# main.net
KiCad netlist of a schematic drawn in Altium Designer
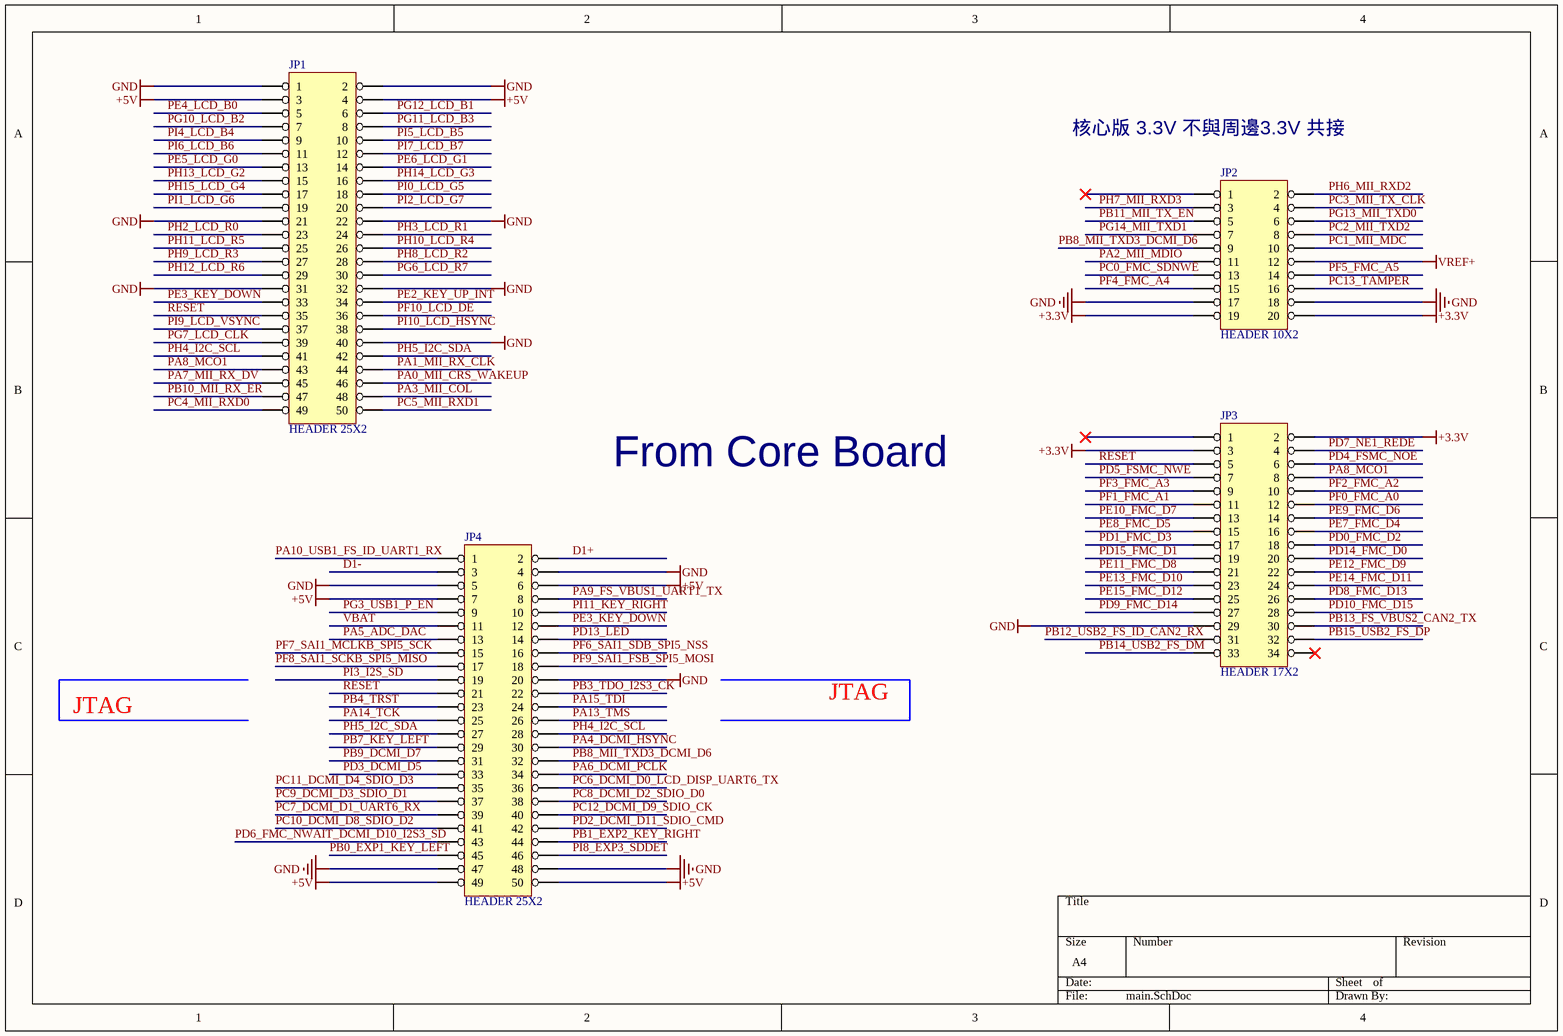
[diagram p0: main.SchDoc]

(export (version "E")
  (design (tool "Eeschema 10.0.6"))
  (components
    (comp (ref "JP1")
      (value "HEADER 25X2")
      (footprint "SIP-50-1.27-SMD")
      (libsource (lib "Mini-STM32F4x9IG-DK-B-SCH") (part "HEADER 25X2"))
    )
    (comp (ref "JP2")
      (value "HEADER 10X2")
      (footprint "SIP-20-1.27-SMD")
      (libsource (lib "Mini-STM32F4x9IG-DK-B-SCH") (part "HEADER 10X2"))
    )
    (comp (ref "JP3")
      (value "HEADER 17X2")
      (footprint "SIP-34-1.27-SMD")
      (libsource (lib "Mini-STM32F4x9IG-DK-B-SCH") (part "HEADER 17X2"))
    )
    (comp (ref "JP4")
      (value "HEADER 25X2")
      (footprint "SIP-50-1.27-SMD")
      (libsource (lib "Mini-STM32F4x9IG-DK-B-SCH") (part "HEADER 25X2"))
    )
  )
  (nets
    (net (code "1") (name "+3.3V") (class "Default")
      (node (ref "JP2") (pin "19") (pinfunction "19_19") (pintype "passive"))
      (node (ref "JP2") (pin "20") (pinfunction "20_20") (pintype "passive"))
      (node (ref "JP3") (pin "2") (pinfunction "2_2") (pintype "passive"))
      (node (ref "JP3") (pin "3") (pinfunction "3_3") (pintype "passive"))
    )
    (net (code "2") (name "+5V") (class "Default")
      (node (ref "JP1") (pin "3") (pinfunction "3_3") (pintype "passive"))
      (node (ref "JP1") (pin "4") (pinfunction "4_4") (pintype "passive"))
      (node (ref "JP4") (pin "49") (pinfunction "49_49") (pintype "passive"))
      (node (ref "JP4") (pin "50") (pinfunction "50_50") (pintype "passive"))
      (node (ref "JP4") (pin "6") (pinfunction "6_6") (pintype "passive"))
      (node (ref "JP4") (pin "7") (pinfunction "7_7") (pintype "passive"))
    )
    (net (code "3") (name "/D1+") (class "Default")
      (node (ref "JP4") (pin "2") (pinfunction "2_2") (pintype "passive"))
    )
    (net (code "4") (name "/D1-") (class "Default")
      (node (ref "JP4") (pin "3") (pinfunction "3_3") (pintype "passive"))
    )
    (net (code "5") (name "/PA0_MII_CRS_WAKEUP") (class "Default")
      (node (ref "JP1") (pin "46") (pinfunction "46_46") (pintype "passive"))
    )
    (net (code "6") (name "/PA1_MII_RX_CLK") (class "Default")
      (node (ref "JP1") (pin "44") (pinfunction "44_44") (pintype "passive"))
    )
    (net (code "7") (name "/PA2_MII_MDIO") (class "Default")
      (node (ref "JP2") (pin "11") (pinfunction "11_11") (pintype "passive"))
    )
    (net (code "8") (name "/PA3_MII_COL") (class "Default")
      (node (ref "JP1") (pin "48") (pinfunction "48_48") (pintype "passive"))
    )
    (net (code "9") (name "/PA4_DCMI_HSYNC") (class "Default")
      (node (ref "JP4") (pin "30") (pinfunction "30_30") (pintype "passive"))
    )
    (net (code "10") (name "/PA5_ADC_DAC") (class "Default")
      (node (ref "JP4") (pin "13") (pinfunction "13_13") (pintype "passive"))
    )
    (net (code "11") (name "/PA6_DCMI_PCLK") (class "Default")
      (node (ref "JP4") (pin "34") (pinfunction "34_34") (pintype "passive"))
    )
    (net (code "12") (name "/PA7_MII_RX_DV") (class "Default")
      (node (ref "JP1") (pin "45") (pinfunction "45_45") (pintype "passive"))
    )
    (net (code "13") (name "/PA8_MCO1") (class "Default")
      (node (ref "JP1") (pin "43") (pinfunction "43_43") (pintype "passive"))
      (node (ref "JP3") (pin "8") (pinfunction "8_8") (pintype "passive"))
    )
    (net (code "14") (name "/PA9_FS_VBUS1_UART1_TX") (class "Default")
      (node (ref "JP4") (pin "8") (pinfunction "8_8") (pintype "passive"))
    )
    (net (code "15") (name "/PA10_USB1_FS_ID_UART1_RX") (class "Default")
      (node (ref "JP4") (pin "1") (pinfunction "1_1") (pintype "passive"))
    )
    (net (code "16") (name "/PA13_TMS") (class "Default")
      (node (ref "JP4") (pin "26") (pinfunction "26_26") (pintype "passive"))
    )
    (net (code "17") (name "/PA14_TCK") (class "Default")
      (node (ref "JP4") (pin "25") (pinfunction "25_25") (pintype "passive"))
    )
    (net (code "18") (name "/PA15_TDI") (class "Default")
      (node (ref "JP4") (pin "24") (pinfunction "24_24") (pintype "passive"))
    )
    (net (code "19") (name "/PB0_EXP1_KEY_LEFT") (class "Default")
      (node (ref "JP4") (pin "45") (pinfunction "45_45") (pintype "passive"))
    )
    (net (code "20") (name "/PB1_EXP2_KEY_RIGHT") (class "Default")
      (node (ref "JP4") (pin "44") (pinfunction "44_44") (pintype "passive"))
    )
    (net (code "21") (name "/PB3_TDO_I2S3_CK") (class "Default")
      (node (ref "JP4") (pin "22") (pinfunction "22_22") (pintype "passive"))
    )
    (net (code "22") (name "/PB4_TRST") (class "Default")
      (node (ref "JP4") (pin "23") (pinfunction "23_23") (pintype "passive"))
    )
    (net (code "23") (name "/PB7_KEY_LEFT") (class "Default")
      (node (ref "JP4") (pin "29") (pinfunction "29_29") (pintype "passive"))
    )
    (net (code "24") (name "/PB8_MII_TXD3_DCMI_D6") (class "Default")
      (node (ref "JP2") (pin "9") (pinfunction "9_9") (pintype "passive"))
      (node (ref "JP4") (pin "32") (pinfunction "32_32") (pintype "passive"))
    )
    (net (code "25") (name "/PB9_DCMI_D7") (class "Default")
      (node (ref "JP4") (pin "31") (pinfunction "31_31") (pintype "passive"))
    )
    (net (code "26") (name "/PB10_MII_RX_ER") (class "Default")
      (node (ref "JP1") (pin "47") (pinfunction "47_47") (pintype "passive"))
    )
    (net (code "27") (name "/PB11_MII_TX_EN") (class "Default")
      (node (ref "JP2") (pin "5") (pinfunction "5_5") (pintype "passive"))
    )
    (net (code "28") (name "/PB12_USB2_FS_ID_CAN2_RX") (class "Default")
      (node (ref "JP3") (pin "31") (pinfunction "31_31") (pintype "passive"))
    )
    (net (code "29") (name "/PB13_FS_VBUS2_CAN2_TX") (class "Default")
      (node (ref "JP3") (pin "30") (pinfunction "30_30") (pintype "passive"))
    )
    (net (code "30") (name "/PB14_USB2_FS_DM") (class "Default")
      (node (ref "JP3") (pin "33") (pinfunction "33_33") (pintype "passive"))
    )
    (net (code "31") (name "/PB15_USB2_FS_DP") (class "Default")
      (node (ref "JP3") (pin "32") (pinfunction "32_32") (pintype "passive"))
    )
    (net (code "32") (name "/PC0_FMC_SDNWE") (class "Default")
      (node (ref "JP2") (pin "13") (pinfunction "13_13") (pintype "passive"))
    )
    (net (code "33") (name "/PC1_MII_MDC") (class "Default")
      (node (ref "JP2") (pin "10") (pinfunction "10_10") (pintype "passive"))
    )
    (net (code "34") (name "/PC2_MII_TXD2") (class "Default")
      (node (ref "JP2") (pin "8") (pinfunction "8_8") (pintype "passive"))
    )
    (net (code "35") (name "/PC3_MII_TX_CLK") (class "Default")
      (node (ref "JP2") (pin "4") (pinfunction "4_4") (pintype "passive"))
    )
    (net (code "36") (name "/PC4_MII_RXD0") (class "Default")
      (node (ref "JP1") (pin "49") (pinfunction "49_49") (pintype "passive"))
    )
    (net (code "37") (name "/PC5_MII_RXD1") (class "Default")
      (node (ref "JP1") (pin "50") (pinfunction "50_50") (pintype "passive"))
    )
    (net (code "38") (name "/PC6_DCMI_D0_LCD_DISP_UART6_TX") (class "Default")
      (node (ref "JP4") (pin "36") (pinfunction "36_36") (pintype "passive"))
    )
    (net (code "39") (name "/PC7_DCMI_D1_UART6_RX") (class "Default")
      (node (ref "JP4") (pin "39") (pinfunction "39_39") (pintype "passive"))
    )
    (net (code "40") (name "/PC8_DCMI_D2_SDIO_D0") (class "Default")
      (node (ref "JP4") (pin "38") (pinfunction "38_38") (pintype "passive"))
    )
    (net (code "41") (name "/PC9_DCMI_D3_SDIO_D1") (class "Default")
      (node (ref "JP4") (pin "37") (pinfunction "37_37") (pintype "passive"))
    )
    (net (code "42") (name "/PC10_DCMI_D8_SDIO_D2") (class "Default")
      (node (ref "JP4") (pin "41") (pinfunction "41_41") (pintype "passive"))
    )
    (net (code "43") (name "/PC11_DCMI_D4_SDIO_D3") (class "Default")
      (node (ref "JP4") (pin "35") (pinfunction "35_35") (pintype "passive"))
    )
    (net (code "44") (name "/PC12_DCMI_D9_SDIO_CK") (class "Default")
      (node (ref "JP4") (pin "40") (pinfunction "40_40") (pintype "passive"))
    )
    (net (code "45") (name "/PC13_TAMPER") (class "Default")
      (node (ref "JP2") (pin "16") (pinfunction "16_16") (pintype "passive"))
    )
    (net (code "46") (name "/PD0_FMC_D2") (class "Default")
      (node (ref "JP3") (pin "18") (pinfunction "18_18") (pintype "passive"))
    )
    (net (code "47") (name "/PD1_FMC_D3") (class "Default")
      (node (ref "JP3") (pin "17") (pinfunction "17_17") (pintype "passive"))
    )
    (net (code "48") (name "/PD2_DCMI_D11_SDIO_CMD") (class "Default")
      (node (ref "JP4") (pin "42") (pinfunction "42_42") (pintype "passive"))
    )
    (net (code "49") (name "/PD3_DCMI_D5") (class "Default")
      (node (ref "JP4") (pin "33") (pinfunction "33_33") (pintype "passive"))
    )
    (net (code "50") (name "/PD4_FSMC_NOE") (class "Default")
      (node (ref "JP3") (pin "6") (pinfunction "6_6") (pintype "passive"))
    )
    (net (code "51") (name "/PD5_FSMC_NWE") (class "Default")
      (node (ref "JP3") (pin "7") (pinfunction "7_7") (pintype "passive"))
    )
    (net (code "52") (name "/PD6_FMC_NWAIT_DCMI_D10_I2S3_SD") (class "Default")
      (node (ref "JP4") (pin "43") (pinfunction "43_43") (pintype "passive"))
    )
    (net (code "53") (name "/PD7_NE1_REDE") (class "Default")
      (node (ref "JP3") (pin "4") (pinfunction "4_4") (pintype "passive"))
    )
    (net (code "54") (name "/PD8_FMC_D13") (class "Default")
      (node (ref "JP3") (pin "26") (pinfunction "26_26") (pintype "passive"))
    )
    (net (code "55") (name "/PD9_FMC_D14") (class "Default")
      (node (ref "JP3") (pin "27") (pinfunction "27_27") (pintype "passive"))
    )
    (net (code "56") (name "/PD10_FMC_D15") (class "Default")
      (node (ref "JP3") (pin "28") (pinfunction "28_28") (pintype "passive"))
    )
    (net (code "57") (name "/PD13_LED") (class "Default")
      (node (ref "JP4") (pin "14") (pinfunction "14_14") (pintype "passive"))
    )
    (net (code "58") (name "/PD14_FMC_D0") (class "Default")
      (node (ref "JP3") (pin "20") (pinfunction "20_20") (pintype "passive"))
    )
    (net (code "59") (name "/PD15_FMC_D1") (class "Default")
      (node (ref "JP3") (pin "19") (pinfunction "19_19") (pintype "passive"))
    )
    (net (code "60") (name "/PE2_KEY_UP_INT") (class "Default")
      (node (ref "JP1") (pin "34") (pinfunction "34_34") (pintype "passive"))
    )
    (net (code "61") (name "/PE3_KEY_DOWN") (class "Default")
      (node (ref "JP1") (pin "33") (pinfunction "33_33") (pintype "passive"))
      (node (ref "JP4") (pin "12") (pinfunction "12_12") (pintype "passive"))
    )
    (net (code "62") (name "/PE4_LCD_B0") (class "Default")
      (node (ref "JP1") (pin "5") (pinfunction "5_5") (pintype "passive"))
    )
    (net (code "63") (name "/PE5_LCD_G0") (class "Default")
      (node (ref "JP1") (pin "13") (pinfunction "13_13") (pintype "passive"))
    )
    (net (code "64") (name "/PE6_LCD_G1") (class "Default")
      (node (ref "JP1") (pin "14") (pinfunction "14_14") (pintype "passive"))
    )
    (net (code "65") (name "/PE7_FMC_D4") (class "Default")
      (node (ref "JP3") (pin "16") (pinfunction "16_16") (pintype "passive"))
    )
    (net (code "66") (name "/PE8_FMC_D5") (class "Default")
      (node (ref "JP3") (pin "15") (pinfunction "15_15") (pintype "passive"))
    )
    (net (code "67") (name "/PE9_FMC_D6") (class "Default")
      (node (ref "JP3") (pin "14") (pinfunction "14_14") (pintype "passive"))
    )
    (net (code "68") (name "/PE10_FMC_D7") (class "Default")
      (node (ref "JP3") (pin "13") (pinfunction "13_13") (pintype "passive"))
    )
    (net (code "69") (name "/PE11_FMC_D8") (class "Default")
      (node (ref "JP3") (pin "21") (pinfunction "21_21") (pintype "passive"))
    )
    (net (code "70") (name "/PE12_FMC_D9") (class "Default")
      (node (ref "JP3") (pin "22") (pinfunction "22_22") (pintype "passive"))
    )
    (net (code "71") (name "/PE13_FMC_D10") (class "Default")
      (node (ref "JP3") (pin "23") (pinfunction "23_23") (pintype "passive"))
    )
    (net (code "72") (name "/PE14_FMC_D11") (class "Default")
      (node (ref "JP3") (pin "24") (pinfunction "24_24") (pintype "passive"))
    )
    (net (code "73") (name "/PE15_FMC_D12") (class "Default")
      (node (ref "JP3") (pin "25") (pinfunction "25_25") (pintype "passive"))
    )
    (net (code "74") (name "/PF0_FMC_A0") (class "Default")
      (node (ref "JP3") (pin "12") (pinfunction "12_12") (pintype "passive"))
    )
    (net (code "75") (name "/PF1_FMC_A1") (class "Default")
      (node (ref "JP3") (pin "11") (pinfunction "11_11") (pintype "passive"))
    )
    (net (code "76") (name "/PF2_FMC_A2") (class "Default")
      (node (ref "JP3") (pin "10") (pinfunction "10_10") (pintype "passive"))
    )
    (net (code "77") (name "/PF3_FMC_A3") (class "Default")
      (node (ref "JP3") (pin "9") (pinfunction "9_9") (pintype "passive"))
    )
    (net (code "78") (name "/PF4_FMC_A4") (class "Default")
      (node (ref "JP2") (pin "15") (pinfunction "15_15") (pintype "passive"))
    )
    (net (code "79") (name "/PF5_FMC_A5") (class "Default")
      (node (ref "JP2") (pin "14") (pinfunction "14_14") (pintype "passive"))
    )
    (net (code "80") (name "/PF6_SAI1_SDB_SPI5_NSS") (class "Default")
      (node (ref "JP4") (pin "16") (pinfunction "16_16") (pintype "passive"))
    )
    (net (code "81") (name "/PF7_SAI1_MCLKB_SPI5_SCK") (class "Default")
      (node (ref "JP4") (pin "15") (pinfunction "15_15") (pintype "passive"))
    )
    (net (code "82") (name "/PF8_SAI1_SCKB_SPI5_MISO") (class "Default")
      (node (ref "JP4") (pin "17") (pinfunction "17_17") (pintype "passive"))
    )
    (net (code "83") (name "/PF9_SAI1_FSB_SPI5_MOSI") (class "Default")
      (node (ref "JP4") (pin "18") (pinfunction "18_18") (pintype "passive"))
    )
    (net (code "84") (name "/PF10_LCD_DE") (class "Default")
      (node (ref "JP1") (pin "36") (pinfunction "36_36") (pintype "passive"))
    )
    (net (code "85") (name "/PG3_USB1_P_EN") (class "Default")
      (node (ref "JP4") (pin "9") (pinfunction "9_9") (pintype "passive"))
    )
    (net (code "86") (name "/PG6_LCD_R7") (class "Default")
      (node (ref "JP1") (pin "30") (pinfunction "30_30") (pintype "passive"))
    )
    (net (code "87") (name "/PG7_LCD_CLK") (class "Default")
      (node (ref "JP1") (pin "39") (pinfunction "39_39") (pintype "passive"))
    )
    (net (code "88") (name "/PG10_LCD_B2") (class "Default")
      (node (ref "JP1") (pin "7") (pinfunction "7_7") (pintype "passive"))
    )
    (net (code "89") (name "/PG11_LCD_B3") (class "Default")
      (node (ref "JP1") (pin "8") (pinfunction "8_8") (pintype "passive"))
    )
    (net (code "90") (name "/PG12_LCD_B1") (class "Default")
      (node (ref "JP1") (pin "6") (pinfunction "6_6") (pintype "passive"))
    )
    (net (code "91") (name "/PG13_MII_TXD0") (class "Default")
      (node (ref "JP2") (pin "6") (pinfunction "6_6") (pintype "passive"))
    )
    (net (code "92") (name "/PG14_MII_TXD1") (class "Default")
      (node (ref "JP2") (pin "7") (pinfunction "7_7") (pintype "passive"))
    )
    (net (code "93") (name "/PH2_LCD_R0") (class "Default")
      (node (ref "JP1") (pin "23") (pinfunction "23_23") (pintype "passive"))
    )
    (net (code "94") (name "/PH3_LCD_R1") (class "Default")
      (node (ref "JP1") (pin "24") (pinfunction "24_24") (pintype "passive"))
    )
    (net (code "95") (name "/PH4_I2C_SCL") (class "Default")
      (node (ref "JP1") (pin "41") (pinfunction "41_41") (pintype "passive"))
      (node (ref "JP4") (pin "28") (pinfunction "28_28") (pintype "passive"))
    )
    (net (code "96") (name "/PH5_I2C_SDA") (class "Default")
      (node (ref "JP1") (pin "42") (pinfunction "42_42") (pintype "passive"))
      (node (ref "JP4") (pin "27") (pinfunction "27_27") (pintype "passive"))
    )
    (net (code "97") (name "/PH6_MII_RXD2") (class "Default")
      (node (ref "JP2") (pin "2") (pinfunction "2_2") (pintype "passive"))
    )
    (net (code "98") (name "/PH7_MII_RXD3") (class "Default")
      (node (ref "JP2") (pin "3") (pinfunction "3_3") (pintype "passive"))
    )
    (net (code "99") (name "/PH8_LCD_R2") (class "Default")
      (node (ref "JP1") (pin "28") (pinfunction "28_28") (pintype "passive"))
    )
    (net (code "100") (name "/PH9_LCD_R3") (class "Default")
      (node (ref "JP1") (pin "27") (pinfunction "27_27") (pintype "passive"))
    )
    (net (code "101") (name "/PH10_LCD_R4") (class "Default")
      (node (ref "JP1") (pin "26") (pinfunction "26_26") (pintype "passive"))
    )
    (net (code "102") (name "/PH11_LCD_R5") (class "Default")
      (node (ref "JP1") (pin "25") (pinfunction "25_25") (pintype "passive"))
    )
    (net (code "103") (name "/PH12_LCD_R6") (class "Default")
      (node (ref "JP1") (pin "29") (pinfunction "29_29") (pintype "passive"))
    )
    (net (code "104") (name "/PH13_LCD_G2") (class "Default")
      (node (ref "JP1") (pin "15") (pinfunction "15_15") (pintype "passive"))
    )
    (net (code "105") (name "/PH14_LCD_G3") (class "Default")
      (node (ref "JP1") (pin "16") (pinfunction "16_16") (pintype "passive"))
    )
    (net (code "106") (name "/PH15_LCD_G4") (class "Default")
      (node (ref "JP1") (pin "17") (pinfunction "17_17") (pintype "passive"))
    )
    (net (code "107") (name "/PI0_LCD_G5") (class "Default")
      (node (ref "JP1") (pin "18") (pinfunction "18_18") (pintype "passive"))
    )
    (net (code "108") (name "/PI1_LCD_G6") (class "Default")
      (node (ref "JP1") (pin "19") (pinfunction "19_19") (pintype "passive"))
    )
    (net (code "109") (name "/PI2_LCD_G7") (class "Default")
      (node (ref "JP1") (pin "20") (pinfunction "20_20") (pintype "passive"))
    )
    (net (code "110") (name "/PI3_I2S_SD") (class "Default")
      (node (ref "JP4") (pin "19") (pinfunction "19_19") (pintype "passive"))
    )
    (net (code "111") (name "/PI4_LCD_B4") (class "Default")
      (node (ref "JP1") (pin "9") (pinfunction "9_9") (pintype "passive"))
    )
    (net (code "112") (name "/PI5_LCD_B5") (class "Default")
      (node (ref "JP1") (pin "10") (pinfunction "10_10") (pintype "passive"))
    )
    (net (code "113") (name "/PI6_LCD_B6") (class "Default")
      (node (ref "JP1") (pin "11") (pinfunction "11_11") (pintype "passive"))
    )
    (net (code "114") (name "/PI7_LCD_B7") (class "Default")
      (node (ref "JP1") (pin "12") (pinfunction "12_12") (pintype "passive"))
    )
    (net (code "115") (name "/PI8_EXP3_SDDET") (class "Default")
      (node (ref "JP4") (pin "46") (pinfunction "46_46") (pintype "passive"))
    )
    (net (code "116") (name "/PI9_LCD_VSYNC") (class "Default")
      (node (ref "JP1") (pin "37") (pinfunction "37_37") (pintype "passive"))
    )
    (net (code "117") (name "/PI10_LCD_HSYNC") (class "Default")
      (node (ref "JP1") (pin "38") (pinfunction "38_38") (pintype "passive"))
    )
    (net (code "118") (name "/PI11_KEY_RIGHT") (class "Default")
      (node (ref "JP4") (pin "10") (pinfunction "10_10") (pintype "passive"))
    )
    (net (code "119") (name "/RESET") (class "Default")
      (node (ref "JP1") (pin "35") (pinfunction "35_35") (pintype "passive"))
      (node (ref "JP3") (pin "5") (pinfunction "5_5") (pintype "passive"))
      (node (ref "JP4") (pin "21") (pinfunction "21_21") (pintype "passive"))
    )
    (net (code "120") (name "/VBAT") (class "Default")
      (node (ref "JP4") (pin "11") (pinfunction "11_11") (pintype "passive"))
    )
    (net (code "121") (name "GND") (class "Default")
      (node (ref "JP1") (pin "1") (pinfunction "1_1") (pintype "passive"))
      (node (ref "JP1") (pin "2") (pinfunction "2_2") (pintype "passive"))
      (node (ref "JP1") (pin "21") (pinfunction "21_21") (pintype "passive"))
      (node (ref "JP1") (pin "22") (pinfunction "22_22") (pintype "passive"))
      (node (ref "JP1") (pin "31") (pinfunction "31_31") (pintype "passive"))
      (node (ref "JP1") (pin "32") (pinfunction "32_32") (pintype "passive"))
      (node (ref "JP1") (pin "40") (pinfunction "40_40") (pintype "passive"))
      (node (ref "JP2") (pin "17") (pinfunction "17_17") (pintype "passive"))
      (node (ref "JP2") (pin "18") (pinfunction "18_18") (pintype "passive"))
      (node (ref "JP3") (pin "29") (pinfunction "29_29") (pintype "passive"))
      (node (ref "JP4") (pin "20") (pinfunction "20_20") (pintype "passive"))
      (node (ref "JP4") (pin "4") (pinfunction "4_4") (pintype "passive"))
      (node (ref "JP4") (pin "47") (pinfunction "47_47") (pintype "passive"))
      (node (ref "JP4") (pin "48") (pinfunction "48_48") (pintype "passive"))
      (node (ref "JP4") (pin "5") (pinfunction "5_5") (pintype "passive"))
    )
    (net (code "122") (name "VREF+") (class "Default")
      (node (ref "JP2") (pin "12") (pinfunction "12_12") (pintype "passive"))
    )
    (net (code "123") (name "unconnected-(JP2-Pad1)") (class "Default")
      (node (ref "JP2") (pin "1") (pinfunction "1_1") (pintype "passive+no_connect"))
    )
    (net (code "124") (name "unconnected-(JP3-Pad1)") (class "Default")
      (node (ref "JP3") (pin "1") (pinfunction "1_1") (pintype "passive+no_connect"))
    )
    (net (code "125") (name "unconnected-(JP3-Pad34)") (class "Default")
      (node (ref "JP3") (pin "34") (pinfunction "34_34") (pintype "passive+no_connect"))
    )
  )
)
